# PCM2707C_HeadPhone_V2.net
KiCad netlist of a schematic drawn in EAGLE
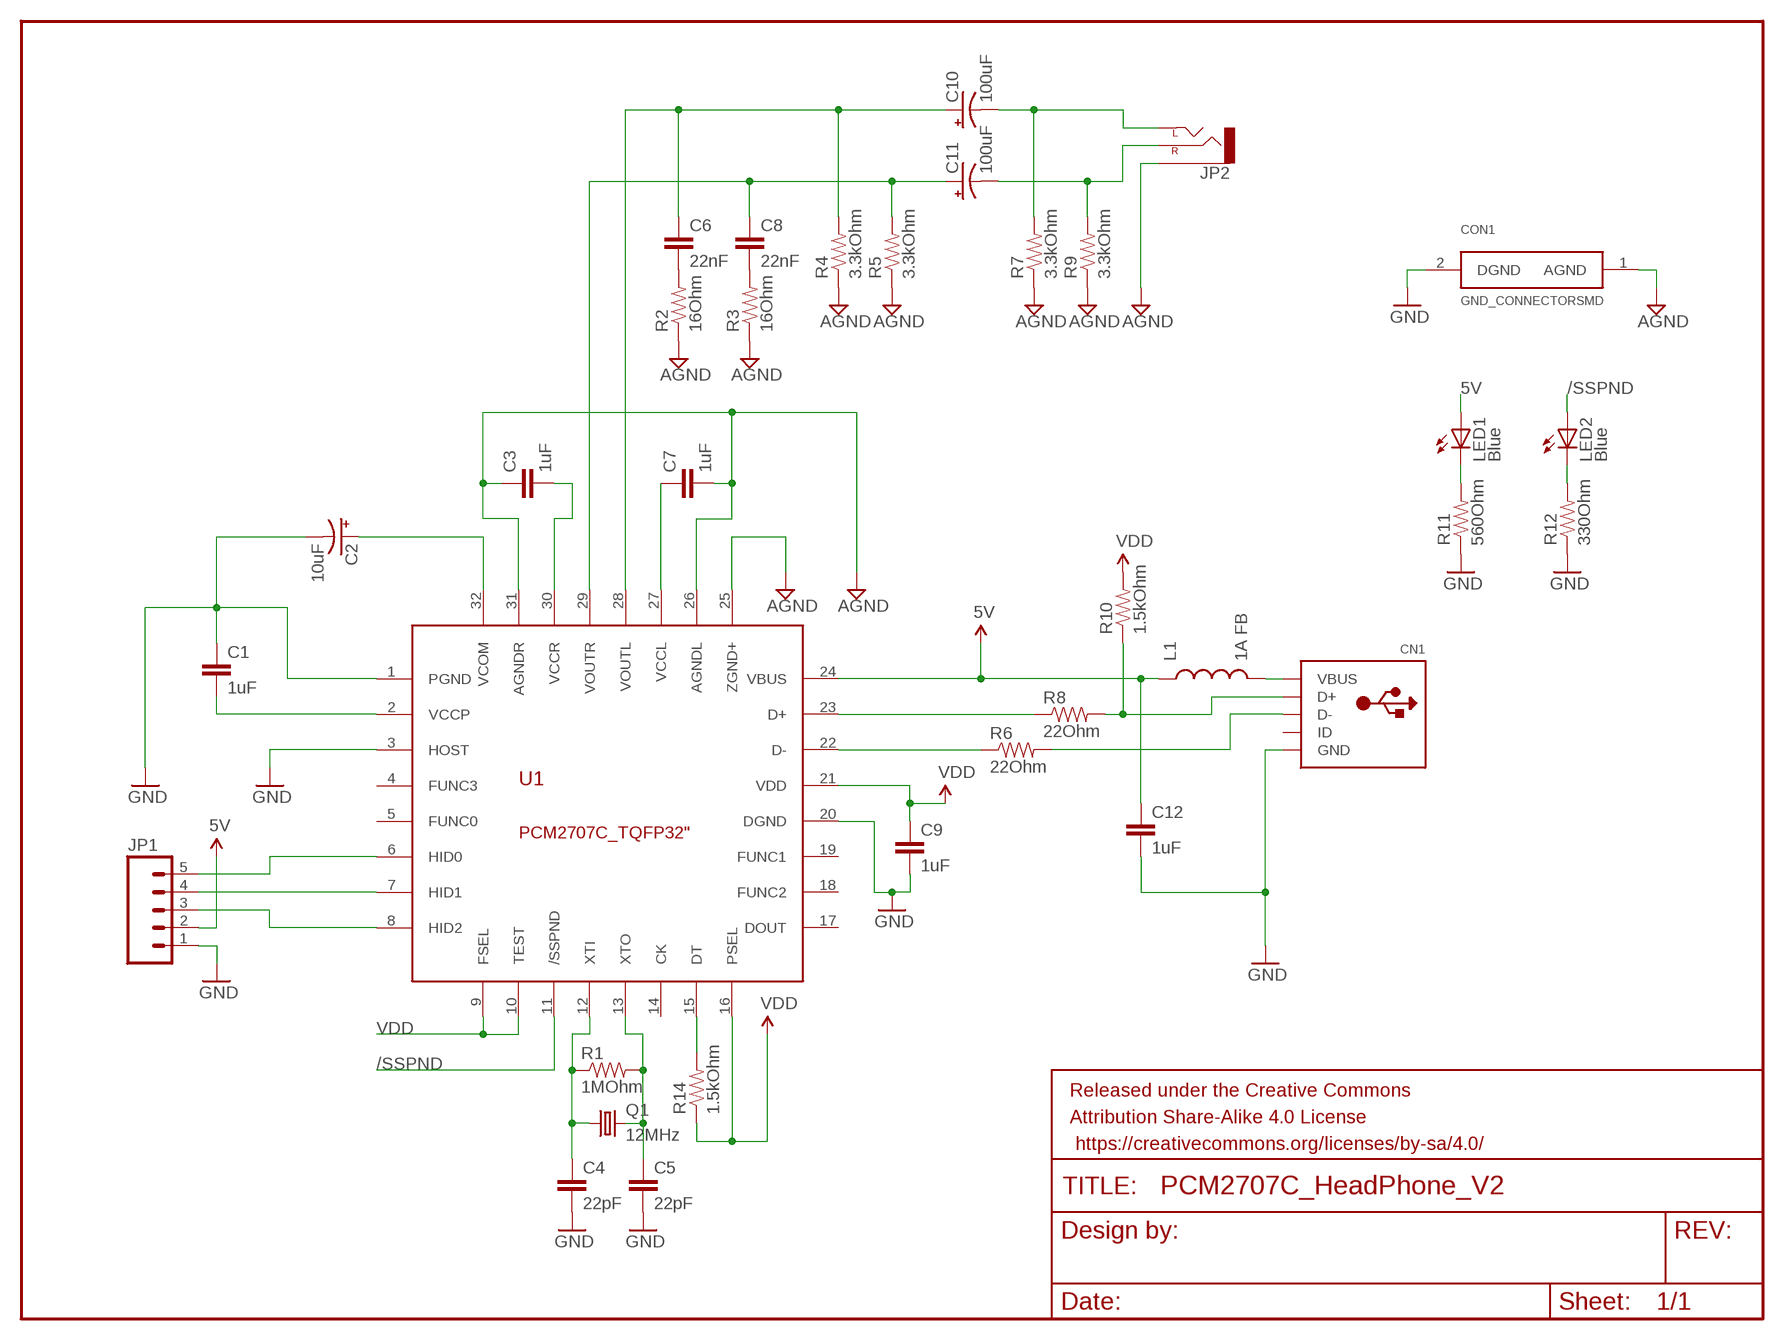
[diagram p0: schematic, sheet 1]

(export (version "E")
  (design (tool "Eeschema 10.0.6"))
  (components
    (comp (ref "C1")
      (value "1uF")
      (footprint "eagle-import:0805")
      (libsource (lib "eagle-import") (part "CAP0805"))
    )
    (comp (ref "C2")
      (value "10uF")
      (footprint "eagle-import:PANASONIC_C")
      (libsource (lib "eagle-import") (part "CAP_POLC"))
    )
    (comp (ref "C3")
      (value "1uF")
      (footprint "eagle-import:0805")
      (libsource (lib "eagle-import") (part "CAP0805"))
    )
    (comp (ref "C4")
      (value "22pF")
      (footprint "eagle-import:0805")
      (libsource (lib "eagle-import") (part "CAP0805"))
    )
    (comp (ref "C5")
      (value "22pF")
      (footprint "eagle-import:0805")
      (libsource (lib "eagle-import") (part "CAP0805"))
    )
    (comp (ref "C6")
      (value "22nF")
      (footprint "eagle-import:0805")
      (libsource (lib "eagle-import") (part "CAP0805"))
    )
    (comp (ref "C7")
      (value "1uF")
      (footprint "eagle-import:0805")
      (libsource (lib "eagle-import") (part "CAP0805"))
    )
    (comp (ref "C8")
      (value "22nF")
      (footprint "eagle-import:0805")
      (libsource (lib "eagle-import") (part "CAP0805"))
    )
    (comp (ref "C9")
      (value "1uF")
      (footprint "eagle-import:0805")
      (libsource (lib "eagle-import") (part "CAP0805"))
    )
    (comp (ref "C10")
      (value "100uF")
      (footprint "eagle-import:PANASONIC_C")
      (libsource (lib "eagle-import") (part "CAP_POLC"))
    )
    (comp (ref "C11")
      (value "100uF")
      (footprint "eagle-import:PANASONIC_C")
      (libsource (lib "eagle-import") (part "CAP_POLC"))
    )
    (comp (ref "C12")
      (value "1uF")
      (footprint "eagle-import:0805")
      (libsource (lib "eagle-import") (part "CAP0805"))
    )
    (comp (ref "CN1")
      (value "USBMOLEX")
      (footprint "eagle-import:USB-MINIB-THM-MOLEX")
      (libsource (lib "eagle-import") (part "USBMOLEX"))
    )
    (comp (ref "CON1")
      (value "GND_CONNECTORSMD")
      (footprint "eagle-import:GND_CONNECTOR")
      (libsource (lib "eagle-import") (part "GND_CONNECTORSMD"))
    )
    (comp (ref "FRAME1")
      (value "FRAME-LETTER")
      (footprint "eagle-import:CREATIVE_COMMONS")
      (libsource (lib "eagle-import") (part "FRAME-LETTER"))
    )
    (comp (ref "JP1")
      (value "M05LOCK")
      (footprint "eagle-import:1X05_LOCK")
      (libsource (lib "eagle-import") (part "M05LOCK"))
    )
    (comp (ref "JP2")
      (value "AUDIO-JACKPTH")
      (footprint "eagle-import:AUDIO-JACK")
      (libsource (lib "eagle-import") (part "AUDIO-JACKPTH"))
    )
    (comp (ref "L1")
      (value "1A FB")
      (footprint "eagle-import:0805")
      (libsource (lib "eagle-import") (part "INDUCTOR0805"))
    )
    (comp (ref "LED1")
      (value "Blue")
      (footprint "eagle-import:LED-0603")
      (libsource (lib "eagle-import") (part "LED0603"))
    )
    (comp (ref "LED2")
      (value "Blue")
      (footprint "eagle-import:LED-0603")
      (libsource (lib "eagle-import") (part "LED0603"))
    )
    (comp (ref "Q1")
      (value "12MHz")
      (footprint "eagle-import:HC49U-V")
      (libsource (lib "eagle-import") (part "CRYSTALHC49U-V"))
    )
    (comp (ref "R1")
      (value "1MOhm")
      (footprint "eagle-import:0805")
      (libsource (lib "eagle-import") (part "RESISTOR0805-RES"))
    )
    (comp (ref "R2")
      (value "16Ohm")
      (footprint "eagle-import:0805")
      (libsource (lib "eagle-import") (part "RESISTOR0805-RES"))
    )
    (comp (ref "R3")
      (value "16Ohm")
      (footprint "eagle-import:0805")
      (libsource (lib "eagle-import") (part "RESISTOR0805-RES"))
    )
    (comp (ref "R4")
      (value "3.3kOhm")
      (footprint "eagle-import:0805")
      (libsource (lib "eagle-import") (part "RESISTOR0805-RES"))
    )
    (comp (ref "R5")
      (value "3.3kOhm")
      (footprint "eagle-import:0805")
      (libsource (lib "eagle-import") (part "RESISTOR0805-RES"))
    )
    (comp (ref "R6")
      (value "22Ohm")
      (footprint "eagle-import:0805")
      (libsource (lib "eagle-import") (part "RESISTOR0805-RES"))
    )
    (comp (ref "R7")
      (value "3.3kOhm")
      (footprint "eagle-import:0805")
      (libsource (lib "eagle-import") (part "RESISTOR0805-RES"))
    )
    (comp (ref "R8")
      (value "22Ohm")
      (footprint "eagle-import:0805")
      (libsource (lib "eagle-import") (part "RESISTOR0805-RES"))
    )
    (comp (ref "R9")
      (value "3.3kOhm")
      (footprint "eagle-import:0805")
      (libsource (lib "eagle-import") (part "RESISTOR0805-RES"))
    )
    (comp (ref "R10")
      (value "1.5kOhm")
      (footprint "eagle-import:0805")
      (libsource (lib "eagle-import") (part "RESISTOR0805-RES"))
    )
    (comp (ref "R11")
      (value "560Ohm")
      (footprint "eagle-import:0805")
      (libsource (lib "eagle-import") (part "RESISTOR0805-RES"))
    )
    (comp (ref "R12")
      (value "330Ohm")
      (footprint "eagle-import:0805")
      (libsource (lib "eagle-import") (part "RESISTOR0805-RES"))
    )
    (comp (ref "R14")
      (value "1.5kOhm")
      (footprint "eagle-import:0805")
      (libsource (lib "eagle-import") (part "RESISTOR0805-RES"))
    )
    (comp (ref "U1")
      (value "PCM2707C_TQFP32\"")
      (footprint "eagle-import:32TQFP_PCM2707C")
      (libsource (lib "eagle-import") (part "PCM2707C_TQFP32{dblquote}"))
    )
  )
  (nets
    (net (code "1") (name "/{slash}SSPND") (class "Default")
      (node (ref "LED2") (pin "A") (pinfunction "A_A") (pintype "passive"))
      (node (ref "U1") (pin "11") (pinfunction "/SSPND_11") (pintype "bidirectional"))
    )
    (net (code "2") (name "5V") (class "Default")
      (node (ref "C12") (pin "1") (pinfunction "1_1") (pintype "passive"))
      (node (ref "JP1") (pin "2") (pinfunction "2_2") (pintype "passive"))
      (node (ref "L1") (pin "1") (pinfunction "1_1") (pintype "passive"))
      (node (ref "LED1") (pin "A") (pinfunction "A_A") (pintype "passive"))
      (node (ref "U1") (pin "24") (pinfunction "VBUS_24") (pintype "bidirectional"))
    )
    (net (code "3") (name "AGND") (class "Default")
      (node (ref "C3") (pin "1") (pinfunction "1_1") (pintype "passive"))
      (node (ref "C7") (pin "2") (pinfunction "2_2") (pintype "passive"))
      (node (ref "CON1") (pin "1") (pinfunction "AGND_1") (pintype "bidirectional"))
      (node (ref "JP2") (pin "SLEEVE") (pinfunction "SLEEVE_SLEEVE") (pintype "bidirectional"))
      (node (ref "R2") (pin "1") (pinfunction "1_1") (pintype "passive"))
      (node (ref "R3") (pin "1") (pinfunction "1_1") (pintype "passive"))
      (node (ref "R4") (pin "1") (pinfunction "1_1") (pintype "passive"))
      (node (ref "R5") (pin "1") (pinfunction "1_1") (pintype "passive"))
      (node (ref "R7") (pin "1") (pinfunction "1_1") (pintype "passive"))
      (node (ref "R9") (pin "1") (pinfunction "1_1") (pintype "passive"))
      (node (ref "U1") (pin "25") (pinfunction "ZGND+_25") (pintype "bidirectional"))
      (node (ref "U1") (pin "26") (pinfunction "AGNDL_26") (pintype "bidirectional"))
      (node (ref "U1") (pin "31") (pinfunction "AGNDR_31") (pintype "bidirectional"))
    )
    (net (code "4") (name "GND") (class "Default")
      (node (ref "C1") (pin "1") (pinfunction "1_1") (pintype "passive"))
      (node (ref "C12") (pin "2") (pinfunction "2_2") (pintype "passive"))
      (node (ref "C2") (pin "-") (pinfunction "-_-") (pintype "passive"))
      (node (ref "C4") (pin "2") (pinfunction "2_2") (pintype "passive"))
      (node (ref "C5") (pin "2") (pinfunction "2_2") (pintype "passive"))
      (node (ref "C9") (pin "2") (pinfunction "2_2") (pintype "passive"))
      (node (ref "CN1") (pin "GND") (pinfunction "GND_GND") (pintype "power_in"))
      (node (ref "CON1") (pin "2") (pinfunction "DGND_2") (pintype "bidirectional"))
      (node (ref "JP1") (pin "1") (pinfunction "1_1") (pintype "passive"))
      (node (ref "R11") (pin "1") (pinfunction "1_1") (pintype "passive"))
      (node (ref "R12") (pin "1") (pinfunction "1_1") (pintype "passive"))
      (node (ref "U1") (pin "1") (pinfunction "PGND_1") (pintype "bidirectional"))
      (node (ref "U1") (pin "20") (pinfunction "DGND_20") (pintype "bidirectional"))
      (node (ref "U1") (pin "3") (pinfunction "HOST_3") (pintype "bidirectional"))
    )
    (net (code "5") (name "Net-(C6-Pad2)") (class "Default")
      (node (ref "C6") (pin "2") (pinfunction "2_2") (pintype "passive"))
      (node (ref "R2") (pin "2") (pinfunction "2_2") (pintype "passive"))
    )
    (net (code "6") (name "Net-(C8-Pad2)") (class "Default")
      (node (ref "C8") (pin "2") (pinfunction "2_2") (pintype "passive"))
      (node (ref "R3") (pin "2") (pinfunction "2_2") (pintype "passive"))
    )
    (net (code "7") (name "Net-(CN1-PadD+)") (class "Default")
      (node (ref "CN1") (pin "D+") (pinfunction "D+_D+") (pintype "bidirectional"))
      (node (ref "R10") (pin "1") (pinfunction "1_1") (pintype "passive"))
      (node (ref "R8") (pin "2") (pinfunction "2_2") (pintype "passive"))
    )
    (net (code "8") (name "Net-(CN1-PadD-)") (class "Default")
      (node (ref "CN1") (pin "D-") (pinfunction "D-_D-") (pintype "bidirectional"))
      (node (ref "R6") (pin "2") (pinfunction "2_2") (pintype "passive"))
    )
    (net (code "9") (name "Net-(CN1-PadVBUS)") (class "Default")
      (node (ref "CN1") (pin "VBUS") (pinfunction "VBUS_VBUS") (pintype "power_in"))
      (node (ref "L1") (pin "2") (pinfunction "2_2") (pintype "passive"))
    )
    (net (code "10") (name "Net-(JP2-LEFT)") (class "Default")
      (node (ref "C10") (pin "-") (pinfunction "-_-") (pintype "passive"))
      (node (ref "JP2") (pin "TIP") (pinfunction "LEFT_TIP") (pintype "bidirectional"))
      (node (ref "R7") (pin "2") (pinfunction "2_2") (pintype "passive"))
    )
    (net (code "11") (name "Net-(JP2-RIGHT)") (class "Default")
      (node (ref "C11") (pin "-") (pinfunction "-_-") (pintype "passive"))
      (node (ref "JP2") (pin "RING") (pinfunction "RIGHT_RING") (pintype "bidirectional"))
      (node (ref "R9") (pin "2") (pinfunction "2_2") (pintype "passive"))
    )
    (net (code "12") (name "Net-(LED1-PadC)") (class "Default")
      (node (ref "LED1") (pin "C") (pinfunction "C_C") (pintype "passive"))
      (node (ref "R11") (pin "2") (pinfunction "2_2") (pintype "passive"))
    )
    (net (code "13") (name "Net-(LED2-PadC)") (class "Default")
      (node (ref "LED2") (pin "C") (pinfunction "C_C") (pintype "passive"))
      (node (ref "R12") (pin "2") (pinfunction "2_2") (pintype "passive"))
    )
    (net (code "14") (name "Net-(U1-D+)") (class "Default")
      (node (ref "R8") (pin "1") (pinfunction "1_1") (pintype "passive"))
      (node (ref "U1") (pin "23") (pinfunction "D+_23") (pintype "bidirectional"))
    )
    (net (code "15") (name "Net-(U1-D-)") (class "Default")
      (node (ref "R6") (pin "1") (pinfunction "1_1") (pintype "passive"))
      (node (ref "U1") (pin "22") (pinfunction "D-_22") (pintype "bidirectional"))
    )
    (net (code "16") (name "Net-(U1-DT)") (class "Default")
      (node (ref "R14") (pin "2") (pinfunction "2_2") (pintype "passive"))
      (node (ref "U1") (pin "15") (pinfunction "DT_15") (pintype "bidirectional"))
    )
    (net (code "17") (name "Net-(U1-HID0)") (class "Default")
      (node (ref "JP1") (pin "5") (pinfunction "5_5") (pintype "passive"))
      (node (ref "U1") (pin "6") (pinfunction "HID0_6") (pintype "bidirectional"))
    )
    (net (code "18") (name "Net-(U1-HID1)") (class "Default")
      (node (ref "JP1") (pin "4") (pinfunction "4_4") (pintype "passive"))
      (node (ref "U1") (pin "7") (pinfunction "HID1_7") (pintype "bidirectional"))
    )
    (net (code "19") (name "Net-(U1-HID2)") (class "Default")
      (node (ref "JP1") (pin "3") (pinfunction "3_3") (pintype "passive"))
      (node (ref "U1") (pin "8") (pinfunction "HID2_8") (pintype "bidirectional"))
    )
    (net (code "20") (name "Net-(U1-VCCL)") (class "Default")
      (node (ref "C7") (pin "1") (pinfunction "1_1") (pintype "passive"))
      (node (ref "U1") (pin "27") (pinfunction "VCCL_27") (pintype "bidirectional"))
    )
    (net (code "21") (name "Net-(U1-VCCP)") (class "Default")
      (node (ref "C1") (pin "2") (pinfunction "2_2") (pintype "passive"))
      (node (ref "U1") (pin "2") (pinfunction "VCCP_2") (pintype "bidirectional"))
    )
    (net (code "22") (name "Net-(U1-VCCR)") (class "Default")
      (node (ref "C3") (pin "2") (pinfunction "2_2") (pintype "passive"))
      (node (ref "U1") (pin "30") (pinfunction "VCCR_30") (pintype "bidirectional"))
    )
    (net (code "23") (name "Net-(U1-VCOM)") (class "Default")
      (node (ref "C2") (pin "+") (pinfunction "+_+") (pintype "passive"))
      (node (ref "U1") (pin "32") (pinfunction "VCOM_32") (pintype "bidirectional"))
    )
    (net (code "24") (name "Net-(U1-VOUTL)") (class "Default")
      (node (ref "C10") (pin "+") (pinfunction "+_+") (pintype "passive"))
      (node (ref "C6") (pin "1") (pinfunction "1_1") (pintype "passive"))
      (node (ref "R4") (pin "2") (pinfunction "2_2") (pintype "passive"))
      (node (ref "U1") (pin "28") (pinfunction "VOUTL_28") (pintype "bidirectional"))
    )
    (net (code "25") (name "Net-(U1-VOUTR)") (class "Default")
      (node (ref "C11") (pin "+") (pinfunction "+_+") (pintype "passive"))
      (node (ref "C8") (pin "1") (pinfunction "1_1") (pintype "passive"))
      (node (ref "R5") (pin "2") (pinfunction "2_2") (pintype "passive"))
      (node (ref "U1") (pin "29") (pinfunction "VOUTR_29") (pintype "bidirectional"))
    )
    (net (code "26") (name "Net-(U1-XTI)") (class "Default")
      (node (ref "C4") (pin "1") (pinfunction "1_1") (pintype "passive"))
      (node (ref "Q1") (pin "1") (pinfunction "1_1") (pintype "passive"))
      (node (ref "R1") (pin "1") (pinfunction "1_1") (pintype "passive"))
      (node (ref "U1") (pin "12") (pinfunction "XTI_12") (pintype "bidirectional"))
    )
    (net (code "27") (name "Net-(U1-XTO)") (class "Default")
      (node (ref "C5") (pin "1") (pinfunction "1_1") (pintype "passive"))
      (node (ref "Q1") (pin "2") (pinfunction "2_2") (pintype "passive"))
      (node (ref "R1") (pin "2") (pinfunction "2_2") (pintype "passive"))
      (node (ref "U1") (pin "13") (pinfunction "XTO_13") (pintype "bidirectional"))
    )
    (net (code "28") (name "VDD") (class "Default")
      (node (ref "C9") (pin "1") (pinfunction "1_1") (pintype "passive"))
      (node (ref "R10") (pin "2") (pinfunction "2_2") (pintype "passive"))
      (node (ref "R14") (pin "1") (pinfunction "1_1") (pintype "passive"))
      (node (ref "U1") (pin "10") (pinfunction "TEST_10") (pintype "bidirectional"))
      (node (ref "U1") (pin "16") (pinfunction "PSEL_16") (pintype "bidirectional"))
      (node (ref "U1") (pin "21") (pinfunction "VDD_21") (pintype "bidirectional"))
      (node (ref "U1") (pin "9") (pinfunction "FSEL_9") (pintype "bidirectional"))
    )
    (net (code "29") (name "unconnected-(CN1-PadID)") (class "Default")
      (node (ref "CN1") (pin "ID") (pinfunction "ID_ID") (pintype "bidirectional"))
    )
    (net (code "30") (name "unconnected-(U1-CK-Pad14)") (class "Default")
      (node (ref "U1") (pin "14") (pinfunction "CK_14") (pintype "bidirectional"))
    )
    (net (code "31") (name "unconnected-(U1-DOUT-Pad17)") (class "Default")
      (node (ref "U1") (pin "17") (pinfunction "DOUT_17") (pintype "bidirectional"))
    )
    (net (code "32") (name "unconnected-(U1-FUNC0-Pad5)") (class "Default")
      (node (ref "U1") (pin "5") (pinfunction "FUNC0_5") (pintype "bidirectional"))
    )
    (net (code "33") (name "unconnected-(U1-FUNC1-Pad19)") (class "Default")
      (node (ref "U1") (pin "19") (pinfunction "FUNC1_19") (pintype "bidirectional"))
    )
    (net (code "34") (name "unconnected-(U1-FUNC2-Pad18)") (class "Default")
      (node (ref "U1") (pin "18") (pinfunction "FUNC2_18") (pintype "bidirectional"))
    )
    (net (code "35") (name "unconnected-(U1-FUNC3-Pad4)") (class "Default")
      (node (ref "U1") (pin "4") (pinfunction "FUNC3_4") (pintype "bidirectional"))
    )
  )
)
